# SCH_CPU.net
KiCad netlist of a schematic drawn in Altium Designer
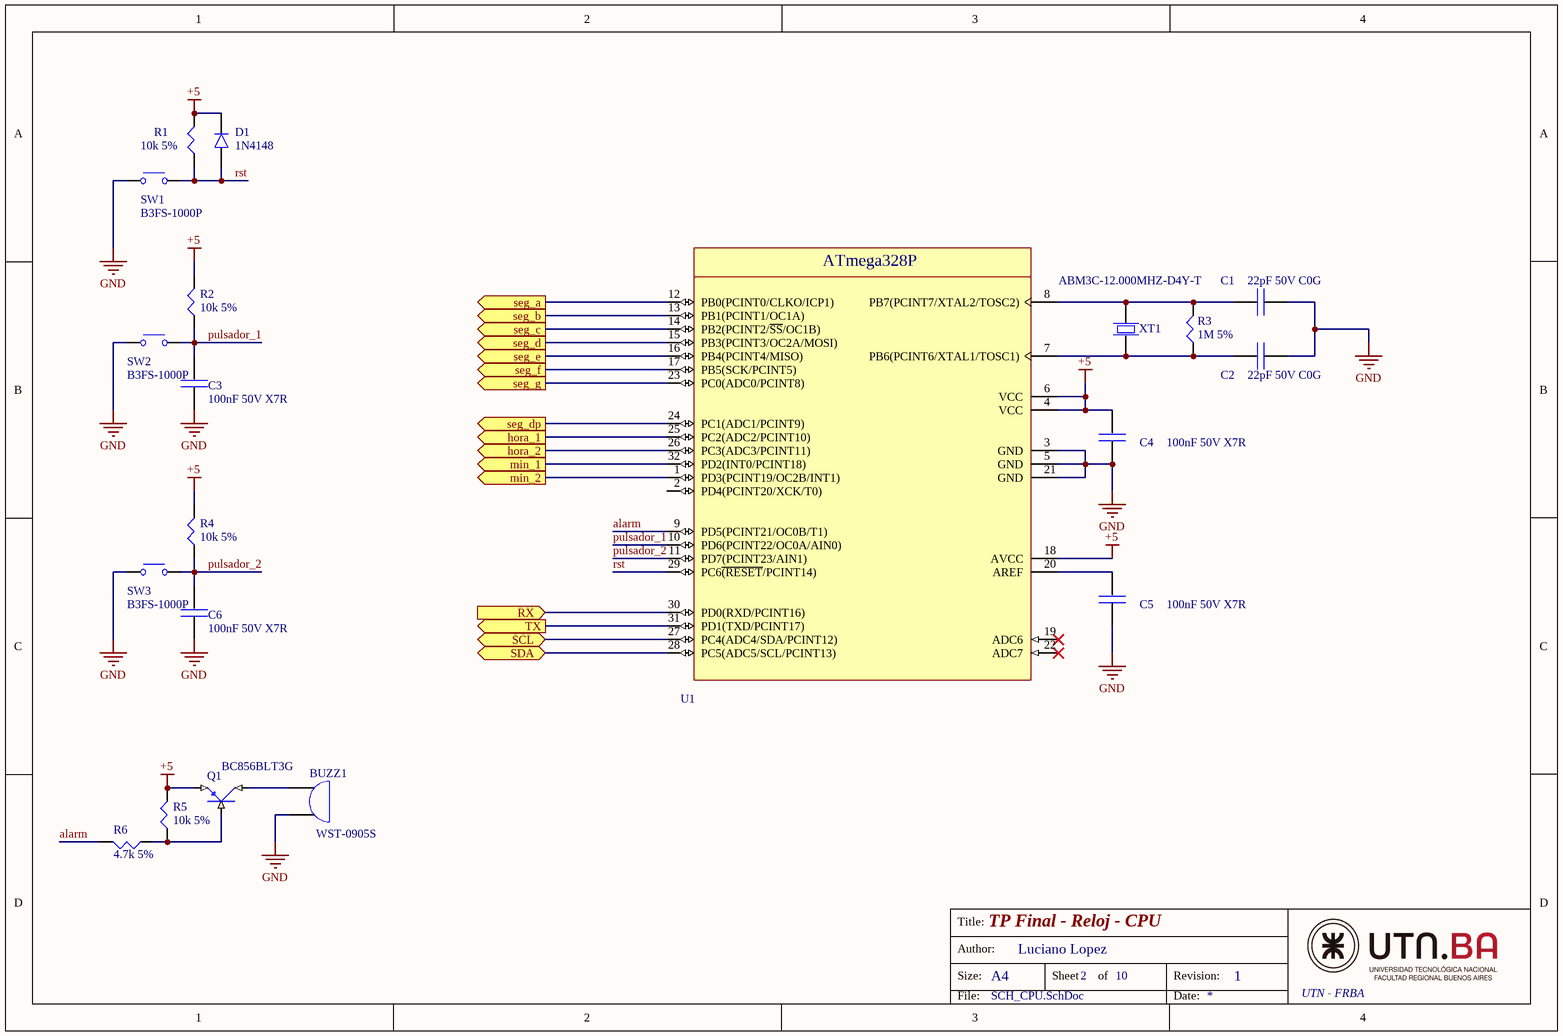
[diagram p0: SCH_CPU.SchDoc]

(export (version "E")
  (design (tool "Eeschema 10.0.6"))
  (components
    (comp (ref "BUZZ1") (value "WST-0905S") (libsource (lib "SCH_LIB") (part "Buzzer")))
    (comp (ref "C1")
      (value "22pF 50V C0G")
      (footprint "C_0805")
      (description "100nF x 50v")
      (libsource (lib "SCH_LIB") (part "Capacitor"))
    )
    (comp (ref "C2")
      (value "22pF 50V C0G")
      (footprint "C_0805")
      (description "100nF x 50v")
      (libsource (lib "SCH_LIB") (part "Capacitor"))
    )
    (comp (ref "C3")
      (value "100nF 50V X7R")
      (footprint "C_0805")
      (description "100nF x 50v")
      (libsource (lib "SCH_LIB") (part "Capacitor"))
    )
    (comp (ref "C4")
      (value "100nF 50V X7R")
      (footprint "C_0805")
      (description "100nF x 50v")
      (libsource (lib "SCH_LIB") (part "Capacitor"))
    )
    (comp (ref "C5")
      (value "100nF 50V X7R")
      (footprint "C_0805")
      (description "100nF x 50v")
      (libsource (lib "SCH_LIB") (part "Capacitor"))
    )
    (comp (ref "C6")
      (value "100nF 50V X7R")
      (footprint "C_0805")
      (description "100nF x 50v")
      (libsource (lib "SCH_LIB") (part "Capacitor"))
    )
    (comp (ref "D1") (value "1N4148") (description "Signal Diode") (libsource (lib "SCH_LIB") (part "Diode")))
    (comp (ref "Q1") (value "BC856BLT3G") (libsource (lib "SCH_LIB") (part "PNP_TRANSISTOR")))
    (comp (ref "R1") (value "10k 5%") (footprint "R_0805") (libsource (lib "SCH_LIB") (part "Resistor")))
    (comp (ref "R2") (value "10k 5%") (footprint "R_0805") (libsource (lib "SCH_LIB") (part "Resistor")))
    (comp (ref "R3") (value "1M 5%") (footprint "R_0805") (libsource (lib "SCH_LIB") (part "Resistor")))
    (comp (ref "R4") (value "10k 5%") (footprint "R_0805") (libsource (lib "SCH_LIB") (part "Resistor")))
    (comp (ref "R5") (value "10k 5%") (footprint "R_0805") (libsource (lib "SCH_LIB") (part "Resistor")))
    (comp (ref "R6") (value "4.7k 5%") (footprint "R_0805") (libsource (lib "SCH_LIB") (part "Resistor")))
    (comp (ref "SW1")
      (value "B3FS-1000P")
      (description "NO Switch")
      (libsource (lib "SCH_LIB") (part "SWITCH"))
    )
    (comp (ref "SW2")
      (value "B3FS-1000P")
      (description "NO Switch")
      (libsource (lib "SCH_LIB") (part "SWITCH"))
    )
    (comp (ref "SW3")
      (value "B3FS-1000P")
      (description "NO Switch")
      (libsource (lib "SCH_LIB") (part "SWITCH"))
    )
    (comp (ref "U1")
      (value "ATMEGA328P-AUR")
      (description "Microcontroller")
      (libsource (lib "SCH_LIB") (part "ATmega328P"))
    )
    (comp (ref "XT1")
      (value "ABM3C-12.000MHZ-D4Y-T")
      (description "crystal piezoelectric")
      (libsource (lib "SCH_LIB") (part "XTAL"))
    )
  )
  (nets
    (net (code "1") (name "+5") (class "Default")
      (node (ref "C4") (pin "39") (pinfunction "39_39") (pintype "passive"))
      (node (ref "D1") (pin "35") (pinfunction "35_35") (pintype "passive"))
      (node (ref "Q1") (pin "3") (pinfunction "E_3") (pintype "input"))
      (node (ref "R1") (pin "48") (pinfunction "48_48") (pintype "passive"))
      (node (ref "R2") (pin "48") (pinfunction "48_48") (pintype "passive"))
      (node (ref "R4") (pin "48") (pinfunction "48_48") (pintype "passive"))
      (node (ref "R5") (pin "48") (pinfunction "48_48") (pintype "passive"))
      (node (ref "U1") (pin "18") (pinfunction "AVCC_18") (pintype "power_in"))
      (node (ref "U1") (pin "4") (pinfunction "VCC_4") (pintype "power_in"))
      (node (ref "U1") (pin "6") (pinfunction "VCC_6") (pintype "power_in"))
    )
    (net (code "2") (name "/RX") (class "Default")
      (node (ref "U1") (pin "30") (pinfunction "PD0(RXD/PCINT16)_30") (pintype "bidirectional"))
    )
    (net (code "3") (name "/SCL") (class "Default")
      (node (ref "U1") (pin "27") (pinfunction "PC4(ADC4/SDA/PCINT12)_27") (pintype "bidirectional"))
    )
    (net (code "4") (name "/SDA") (class "Default")
      (node (ref "U1") (pin "28") (pinfunction "PC5(ADC5/SCL/PCINT13)_28") (pintype "bidirectional"))
    )
    (net (code "5") (name "/TX") (class "Default")
      (node (ref "U1") (pin "31") (pinfunction "PD1(TXD/PCINT17)_31") (pintype "bidirectional"))
    )
    (net (code "6") (name "/alarm") (class "Default")
      (node (ref "R6") (pin "48") (pinfunction "48_48") (pintype "passive"))
      (node (ref "U1") (pin "9") (pinfunction "PD5(PCINT21/OC0B/T1)_9") (pintype "bidirectional"))
    )
    (net (code "7") (name "/hora_1") (class "Default")
      (node (ref "U1") (pin "25") (pinfunction "PC2(ADC2/PCINT10)_25") (pintype "bidirectional"))
    )
    (net (code "8") (name "/hora_2") (class "Default")
      (node (ref "U1") (pin "26") (pinfunction "PC3(ADC3/PCINT11)_26") (pintype "bidirectional"))
    )
    (net (code "9") (name "/min_1") (class "Default")
      (node (ref "U1") (pin "32") (pinfunction "PD2(INT0/PCINT18)_32") (pintype "bidirectional"))
    )
    (net (code "10") (name "/min_2") (class "Default")
      (node (ref "U1") (pin "1") (pinfunction "PD3(PCINT19/OC2B/INT1)_1") (pintype "bidirectional"))
    )
    (net (code "11") (name "/pulsador_1") (class "Default")
      (node (ref "C3") (pin "39") (pinfunction "39_39") (pintype "passive"))
      (node (ref "R2") (pin "47") (pinfunction "47_47") (pintype "passive"))
      (node (ref "SW2") (pin "6") (pinfunction "6_6") (pintype "passive"))
      (node (ref "U1") (pin "10") (pinfunction "PD6(PCINT22/OC0A/AIN0)_10") (pintype "bidirectional"))
    )
    (net (code "12") (name "/pulsador_2") (class "Default")
      (node (ref "C6") (pin "39") (pinfunction "39_39") (pintype "passive"))
      (node (ref "R4") (pin "47") (pinfunction "47_47") (pintype "passive"))
      (node (ref "SW3") (pin "6") (pinfunction "6_6") (pintype "passive"))
      (node (ref "U1") (pin "11") (pinfunction "PD7(PCINT23/AIN1)_11") (pintype "bidirectional"))
    )
    (net (code "13") (name "/rst") (class "Default")
      (node (ref "D1") (pin "34") (pinfunction "34_34") (pintype "passive"))
      (node (ref "R1") (pin "47") (pinfunction "47_47") (pintype "passive"))
      (node (ref "SW1") (pin "6") (pinfunction "6_6") (pintype "passive"))
      (node (ref "U1") (pin "29") (pinfunction "PC6~{(RESET}/PCINT14)_29") (pintype "bidirectional"))
    )
    (net (code "14") (name "/seg_a") (class "Default")
      (node (ref "U1") (pin "12") (pinfunction "PB0(PCINT0/CLKO/ICP1)_12") (pintype "bidirectional"))
    )
    (net (code "15") (name "/seg_b") (class "Default")
      (node (ref "U1") (pin "13") (pinfunction "PB1(PCINT1/OC1A)_13") (pintype "bidirectional"))
    )
    (net (code "16") (name "/seg_c") (class "Default")
      (node (ref "U1") (pin "14") (pinfunction "PB2(PCINT2/~{SS}/OC1B)_14") (pintype "bidirectional"))
    )
    (net (code "17") (name "/seg_d") (class "Default")
      (node (ref "U1") (pin "15") (pinfunction "PB3(PCINT3/OC2A/MOSI)_15") (pintype "bidirectional"))
    )
    (net (code "18") (name "/seg_dp") (class "Default")
      (node (ref "U1") (pin "24") (pinfunction "PC1(ADC1/PCINT9)_24") (pintype "bidirectional"))
    )
    (net (code "19") (name "/seg_e") (class "Default")
      (node (ref "U1") (pin "16") (pinfunction "PB4(PCINT4/MISO)_16") (pintype "bidirectional"))
    )
    (net (code "20") (name "/seg_f") (class "Default")
      (node (ref "U1") (pin "17") (pinfunction "PB5(SCK/PCINT5)_17") (pintype "bidirectional"))
    )
    (net (code "21") (name "/seg_g") (class "Default")
      (node (ref "U1") (pin "23") (pinfunction "PC0(ADC0/PCINT8)_23") (pintype "bidirectional"))
    )
    (net (code "22") (name "GND") (class "Default")
      (node (ref "BUZZ1") (pin "27") (pinfunction "27_27") (pintype "passive"))
      (node (ref "C1") (pin "38") (pinfunction "38_38") (pintype "passive"))
      (node (ref "C2") (pin "38") (pinfunction "38_38") (pintype "passive"))
      (node (ref "C3") (pin "38") (pinfunction "38_38") (pintype "passive"))
      (node (ref "C4") (pin "38") (pinfunction "38_38") (pintype "passive"))
      (node (ref "C5") (pin "38") (pinfunction "38_38") (pintype "passive"))
      (node (ref "C6") (pin "38") (pinfunction "38_38") (pintype "passive"))
      (node (ref "SW1") (pin "7") (pinfunction "7_7") (pintype "passive"))
      (node (ref "SW2") (pin "7") (pinfunction "7_7") (pintype "passive"))
      (node (ref "SW3") (pin "7") (pinfunction "7_7") (pintype "passive"))
      (node (ref "U1") (pin "21") (pinfunction "GND_21") (pintype "power_in"))
      (node (ref "U1") (pin "3") (pinfunction "GND_3") (pintype "power_in"))
      (node (ref "U1") (pin "5") (pinfunction "GND_5") (pintype "power_in"))
    )
    (net (code "23") (name "Net-(Q1-B)") (class "Default")
      (node (ref "Q1") (pin "1") (pinfunction "B_1") (pintype "input"))
      (node (ref "R5") (pin "47") (pinfunction "47_47") (pintype "passive"))
      (node (ref "R6") (pin "47") (pinfunction "47_47") (pintype "passive"))
    )
    (net (code "24") (name "Net-(Q1-C)") (class "Default")
      (node (ref "BUZZ1") (pin "26") (pinfunction "26_26") (pintype "passive"))
      (node (ref "Q1") (pin "2") (pinfunction "C_2") (pintype "input"))
    )
    (net (code "25") (name "Net-(U1-AREF)") (class "Default")
      (node (ref "C5") (pin "39") (pinfunction "39_39") (pintype "passive"))
      (node (ref "U1") (pin "20") (pinfunction "AREF_20") (pintype "power_in"))
    )
    (net (code "26") (name "Net-(U1-PB6(PCINT6{slash}XTAL1{slash}TOSC1))") (class "Default")
      (node (ref "C2") (pin "39") (pinfunction "39_39") (pintype "passive"))
      (node (ref "R3") (pin "47") (pinfunction "47_47") (pintype "passive"))
      (node (ref "U1") (pin "7") (pinfunction "PB6(PCINT6/XTAL1/TOSC1)_7") (pintype "passive"))
      (node (ref "XT1") (pin "5") (pinfunction "5_5") (pintype "passive"))
    )
    (net (code "27") (name "Net-(U1-PB7(PCINT7{slash}XTAL2{slash}TOSC2))") (class "Default")
      (node (ref "C1") (pin "39") (pinfunction "39_39") (pintype "passive"))
      (node (ref "R3") (pin "48") (pinfunction "48_48") (pintype "passive"))
      (node (ref "U1") (pin "8") (pinfunction "PB7(PCINT7/XTAL2/TOSC2)_8") (pintype "passive"))
      (node (ref "XT1") (pin "4") (pinfunction "4_4") (pintype "passive"))
    )
    (net (code "28") (name "unconnected-(U1-ADC6-Pad19)") (class "Default")
      (node (ref "U1") (pin "19") (pinfunction "ADC6_19") (pintype "input+no_connect"))
    )
    (net (code "29") (name "unconnected-(U1-ADC7-Pad22)") (class "Default")
      (node (ref "U1") (pin "22") (pinfunction "ADC7_22") (pintype "input+no_connect"))
    )
    (net (code "30") (name "unconnected-(U1-PD4(PCINT20{slash}XCK{slash}T0)-Pad2)") (class "Default")
      (node (ref "U1") (pin "2") (pinfunction "PD4(PCINT20/XCK/T0)_2") (pintype "bidirectional"))
    )
  )
)
